# Bluetooth.net
KiCad netlist of a schematic drawn in Altium Designer
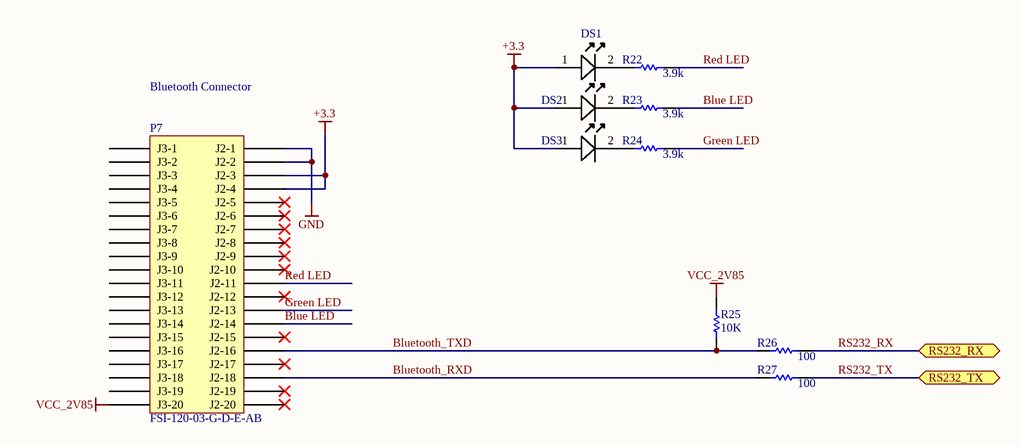
[diagram p0: Bluetooth.SchDoc]

(export (version "E")
  (design (tool "Eeschema 10.0.6"))
  (components
    (comp (ref "DS1")
      (value "Lite-On LTST-S220KGKT Green LED, 571 nm 2012 (0805) Side View, Rectangle Lens SMD package")
      (footprint "0805C_L")
      (fields
        (field (name "MANUFACTURER") "Vishay / Lite-On")
        (field (name "MANUFACTURER PART NUMBER") "LTST-S220KGKT")
      )
      (libsource (lib "*") (part "LED A/K"))
    )
    (comp (ref "DS2")
      (value "Lite-On LTST-S220KGKT Green LED, 571 nm 2012 (0805) Side View, Rectangle Lens SMD package")
      (footprint "0805C_L")
      (fields
        (field (name "MANUFACTURER") "Vishay / Lite-On")
        (field (name "MANUFACTURER PART NUMBER") "LTST-S220KGKT")
      )
      (libsource (lib "*") (part "LED A/K"))
    )
    (comp (ref "DS3")
      (value "Lite-On LTST-S220KGKT Green LED, 571 nm 2012 (0805) Side View, Rectangle Lens SMD package")
      (footprint "0805C_L")
      (fields
        (field (name "MANUFACTURER") "Vishay / Lite-On")
        (field (name "MANUFACTURER PART NUMBER") "LTST-S220KGKT")
      )
      (libsource (lib "*") (part "LED A/K"))
    )
    (comp (ref "P7")
      (value "FSI-120-03-G-D-E-AB")
      (footprint "FSI-120-03-G-D-E-AB")
      (fields (field (name "SUPPLIER PART NUMBER 1") "FSI-120-03-G-D-E-AB"))
      (libsource (lib "ZLS_Schematic_lib") (part "FSI-120-03-G-D-E-AB"))
    )
    (comp (ref "R22")
      (value "3.9k")
      (footprint "RESC0805(2012)_L")
      (description "2R55 0.125W 1% 0805 (2012 Metric)  SMD")
      (fields (field (name "TOLERANCE") "1 %") (field (name "POWER") "0.125 W"))
      (libsource (lib "Altium Content Vault") (part "CMP-1013-00215-1"))
    )
    (comp (ref "R23")
      (value "3.9k")
      (footprint "RESC0805(2012)_L")
      (description "2R55 0.125W 1% 0805 (2012 Metric)  SMD")
      (fields (field (name "TOLERANCE") "1 %") (field (name "POWER") "0.125 W"))
      (libsource (lib "Altium Content Vault") (part "CMP-1013-00215-1"))
    )
    (comp (ref "R24")
      (value "3.9k")
      (footprint "RESC0805(2012)_L")
      (description "2R55 0.125W 1% 0805 (2012 Metric)  SMD")
      (fields (field (name "TOLERANCE") "1 %") (field (name "POWER") "0.125 W"))
      (libsource (lib "Altium Content Vault") (part "CMP-1013-00215-1"))
    )
    (comp (ref "R25")
      (value "10K")
      (footprint "RESC0805(2012)_L")
      (description "2R55 0.125W 1% 0805 (2012 Metric)  SMD")
      (fields (field (name "TOLERANCE") "1 %") (field (name "POWER") "0.125 W"))
      (libsource (lib "Altium Content Vault") (part "CMP-1013-00215-1"))
    )
    (comp (ref "R26")
      (value "100")
      (footprint "RESC0805(2012)_L")
      (description "2R55 0.125W 1% 0805 (2012 Metric)  SMD")
      (fields (field (name "TOLERANCE") "1 %") (field (name "POWER") "0.125 W"))
      (libsource (lib "Altium Content Vault") (part "CMP-1013-00215-1"))
    )
    (comp (ref "R27")
      (value "100")
      (footprint "RESC0805(2012)_L")
      (description "2R55 0.125W 1% 0805 (2012 Metric)  SMD")
      (fields (field (name "TOLERANCE") "1 %") (field (name "POWER") "0.125 W"))
      (libsource (lib "Altium Content Vault") (part "CMP-1013-00215-1"))
    )
  )
  (nets
    (net (code "1") (name "+3.3") (class "Default")
      (node (ref "DS1") (pin "1") (pinfunction "A_1") (pintype "passive"))
      (node (ref "DS2") (pin "1") (pinfunction "A_1") (pintype "passive"))
      (node (ref "DS3") (pin "1") (pinfunction "A_1") (pintype "passive"))
      (node (ref "P7") (pin "J2-3") (pinfunction "J2-3_J2-3") (pintype "passive"))
      (node (ref "P7") (pin "J2-4") (pinfunction "J2-4_J2-4") (pintype "passive"))
    )
    (net (code "2") (name "/Blue LED") (class "Default")
      (node (ref "P7") (pin "J2-14") (pinfunction "J2-14_J2-14") (pintype "passive"))
      (node (ref "R23") (pin "1") (pinfunction "1_1") (pintype "passive"))
    )
    (net (code "3") (name "/Bluetooth_RXD") (class "Default")
      (node (ref "P7") (pin "J2-18") (pinfunction "J2-18_J2-18") (pintype "passive"))
      (node (ref "R27") (pin "2") (pinfunction "2_2") (pintype "passive"))
    )
    (net (code "4") (name "/Bluetooth_TXD") (class "Default")
      (node (ref "P7") (pin "J2-16") (pinfunction "J2-16_J2-16") (pintype "passive"))
      (node (ref "R25") (pin "2") (pinfunction "2_2") (pintype "passive"))
      (node (ref "R26") (pin "2") (pinfunction "2_2") (pintype "passive"))
    )
    (net (code "5") (name "/Green LED") (class "Default")
      (node (ref "P7") (pin "J2-13") (pinfunction "J2-13_J2-13") (pintype "passive"))
      (node (ref "R24") (pin "1") (pinfunction "1_1") (pintype "passive"))
    )
    (net (code "6") (name "/RS232_RX") (class "Default")
      (node (ref "R26") (pin "1") (pinfunction "1_1") (pintype "passive"))
    )
    (net (code "7") (name "/RS232_TX") (class "Default")
      (node (ref "R27") (pin "1") (pinfunction "1_1") (pintype "passive"))
    )
    (net (code "8") (name "/Red LED") (class "Default")
      (node (ref "P7") (pin "J2-11") (pinfunction "J2-11_J2-11") (pintype "passive"))
      (node (ref "R22") (pin "1") (pinfunction "1_1") (pintype "passive"))
    )
    (net (code "9") (name "GND") (class "Default")
      (node (ref "P7") (pin "J2-1") (pinfunction "J2-1_J2-1") (pintype "passive"))
      (node (ref "P7") (pin "J2-2") (pinfunction "J2-2_J2-2") (pintype "passive"))
    )
    (net (code "10") (name "Net-(DS1-K)") (class "Default")
      (node (ref "DS1") (pin "2") (pinfunction "K_2") (pintype "passive"))
      (node (ref "R22") (pin "2") (pinfunction "2_2") (pintype "passive"))
    )
    (net (code "11") (name "Net-(DS2-K)") (class "Default")
      (node (ref "DS2") (pin "2") (pinfunction "K_2") (pintype "passive"))
      (node (ref "R23") (pin "2") (pinfunction "2_2") (pintype "passive"))
    )
    (net (code "12") (name "Net-(DS3-K)") (class "Default")
      (node (ref "DS3") (pin "2") (pinfunction "K_2") (pintype "passive"))
      (node (ref "R24") (pin "2") (pinfunction "2_2") (pintype "passive"))
    )
    (net (code "13") (name "VCC_2V85") (class "Default")
      (node (ref "P7") (pin "J3-20") (pinfunction "J3-20_J3-20") (pintype "passive"))
      (node (ref "R25") (pin "1") (pinfunction "1_1") (pintype "passive"))
    )
    (net (code "14") (name "unconnected-(P7-PadJ2-5)") (class "Default")
      (node (ref "P7") (pin "J2-5") (pinfunction "J2-5_J2-5") (pintype "passive+no_connect"))
    )
    (net (code "15") (name "unconnected-(P7-PadJ2-6)") (class "Default")
      (node (ref "P7") (pin "J2-6") (pinfunction "J2-6_J2-6") (pintype "passive+no_connect"))
    )
    (net (code "16") (name "unconnected-(P7-PadJ2-7)") (class "Default")
      (node (ref "P7") (pin "J2-7") (pinfunction "J2-7_J2-7") (pintype "passive+no_connect"))
    )
    (net (code "17") (name "unconnected-(P7-PadJ2-8)") (class "Default")
      (node (ref "P7") (pin "J2-8") (pinfunction "J2-8_J2-8") (pintype "passive+no_connect"))
    )
    (net (code "18") (name "unconnected-(P7-PadJ2-9)") (class "Default")
      (node (ref "P7") (pin "J2-9") (pinfunction "J2-9_J2-9") (pintype "passive+no_connect"))
    )
    (net (code "19") (name "unconnected-(P7-PadJ2-10)") (class "Default")
      (node (ref "P7") (pin "J2-10") (pinfunction "J2-10_J2-10") (pintype "passive+no_connect"))
    )
    (net (code "20") (name "unconnected-(P7-PadJ2-12)") (class "Default")
      (node (ref "P7") (pin "J2-12") (pinfunction "J2-12_J2-12") (pintype "passive+no_connect"))
    )
    (net (code "21") (name "unconnected-(P7-PadJ2-15)") (class "Default")
      (node (ref "P7") (pin "J2-15") (pinfunction "J2-15_J2-15") (pintype "passive+no_connect"))
    )
    (net (code "22") (name "unconnected-(P7-PadJ2-17)") (class "Default")
      (node (ref "P7") (pin "J2-17") (pinfunction "J2-17_J2-17") (pintype "passive+no_connect"))
    )
    (net (code "23") (name "unconnected-(P7-PadJ2-19)") (class "Default")
      (node (ref "P7") (pin "J2-19") (pinfunction "J2-19_J2-19") (pintype "passive+no_connect"))
    )
    (net (code "24") (name "unconnected-(P7-PadJ2-20)") (class "Default")
      (node (ref "P7") (pin "J2-20") (pinfunction "J2-20_J2-20") (pintype "passive+no_connect"))
    )
    (net (code "25") (name "unconnected-(P7-PadJ3-1)") (class "Default")
      (node (ref "P7") (pin "J3-1") (pinfunction "J3-1_J3-1") (pintype "passive"))
    )
    (net (code "26") (name "unconnected-(P7-PadJ3-2)") (class "Default")
      (node (ref "P7") (pin "J3-2") (pinfunction "J3-2_J3-2") (pintype "passive"))
    )
    (net (code "27") (name "unconnected-(P7-PadJ3-3)") (class "Default")
      (node (ref "P7") (pin "J3-3") (pinfunction "J3-3_J3-3") (pintype "passive"))
    )
    (net (code "28") (name "unconnected-(P7-PadJ3-4)") (class "Default")
      (node (ref "P7") (pin "J3-4") (pinfunction "J3-4_J3-4") (pintype "passive"))
    )
    (net (code "29") (name "unconnected-(P7-PadJ3-5)") (class "Default")
      (node (ref "P7") (pin "J3-5") (pinfunction "J3-5_J3-5") (pintype "passive"))
    )
    (net (code "30") (name "unconnected-(P7-PadJ3-6)") (class "Default")
      (node (ref "P7") (pin "J3-6") (pinfunction "J3-6_J3-6") (pintype "passive"))
    )
    (net (code "31") (name "unconnected-(P7-PadJ3-7)") (class "Default")
      (node (ref "P7") (pin "J3-7") (pinfunction "J3-7_J3-7") (pintype "passive"))
    )
    (net (code "32") (name "unconnected-(P7-PadJ3-8)") (class "Default")
      (node (ref "P7") (pin "J3-8") (pinfunction "J3-8_J3-8") (pintype "passive"))
    )
    (net (code "33") (name "unconnected-(P7-PadJ3-9)") (class "Default")
      (node (ref "P7") (pin "J3-9") (pinfunction "J3-9_J3-9") (pintype "passive"))
    )
    (net (code "34") (name "unconnected-(P7-PadJ3-10)") (class "Default")
      (node (ref "P7") (pin "J3-10") (pinfunction "J3-10_J3-10") (pintype "passive"))
    )
    (net (code "35") (name "unconnected-(P7-PadJ3-11)") (class "Default")
      (node (ref "P7") (pin "J3-11") (pinfunction "J3-11_J3-11") (pintype "passive"))
    )
    (net (code "36") (name "unconnected-(P7-PadJ3-12)") (class "Default")
      (node (ref "P7") (pin "J3-12") (pinfunction "J3-12_J3-12") (pintype "passive"))
    )
    (net (code "37") (name "unconnected-(P7-PadJ3-13)") (class "Default")
      (node (ref "P7") (pin "J3-13") (pinfunction "J3-13_J3-13") (pintype "passive"))
    )
    (net (code "38") (name "unconnected-(P7-PadJ3-14)") (class "Default")
      (node (ref "P7") (pin "J3-14") (pinfunction "J3-14_J3-14") (pintype "passive"))
    )
    (net (code "39") (name "unconnected-(P7-PadJ3-15)") (class "Default")
      (node (ref "P7") (pin "J3-15") (pinfunction "J3-15_J3-15") (pintype "passive"))
    )
    (net (code "40") (name "unconnected-(P7-PadJ3-16)") (class "Default")
      (node (ref "P7") (pin "J3-16") (pinfunction "J3-16_J3-16") (pintype "passive"))
    )
    (net (code "41") (name "unconnected-(P7-PadJ3-17)") (class "Default")
      (node (ref "P7") (pin "J3-17") (pinfunction "J3-17_J3-17") (pintype "passive"))
    )
    (net (code "42") (name "unconnected-(P7-PadJ3-18)") (class "Default")
      (node (ref "P7") (pin "J3-18") (pinfunction "J3-18_J3-18") (pintype "passive"))
    )
    (net (code "43") (name "unconnected-(P7-PadJ3-19)") (class "Default")
      (node (ref "P7") (pin "J3-19") (pinfunction "J3-19_J3-19") (pintype "passive"))
    )
  )
)
